# USB.net
KiCad netlist of a schematic drawn in Altium Designer
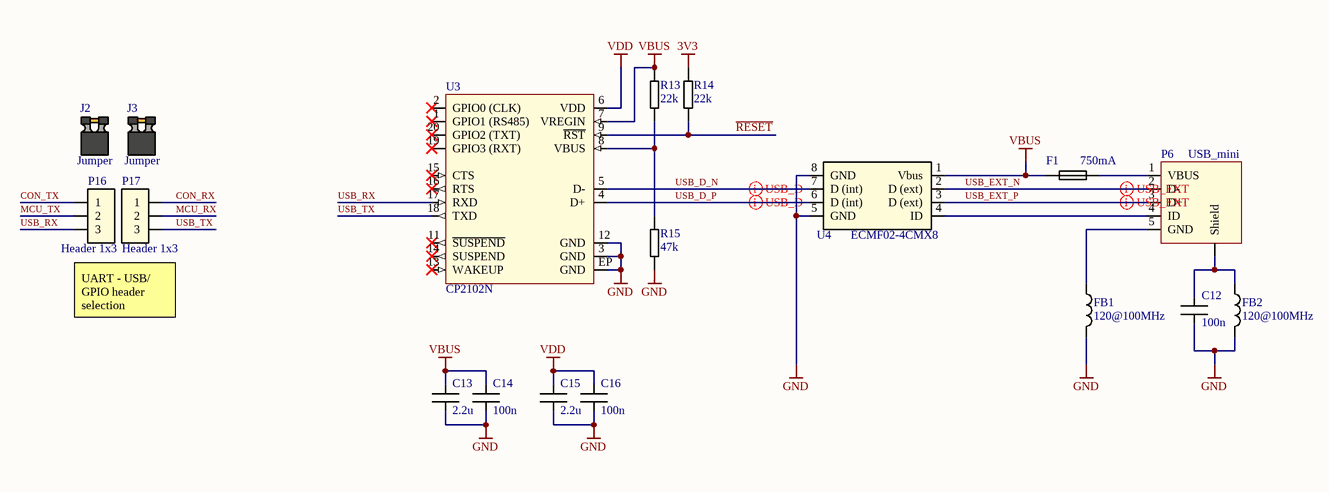
[diagram p0: USB.SchDoc]

(export (version "E")
  (design (tool "Eeschema 10.0.6"))
  (components
    (comp (ref "C12")
      (value "100n")
      (footprint "CAPC1005N")
      (description "0402 SMD Capacitor")
      (fields (field (name "TOLERANCE") "10%"))
      (libsource (lib "RLC") (part "Capacitor"))
    )
    (comp (ref "C13")
      (value "2.2u")
      (footprint "CAPC1005N")
      (description "0402 SMD Capacitor")
      (fields (field (name "TOLERANCE") "10%") (field (name "Comment") "Capacitor"))
      (libsource (lib "RLC") (part "Capacitor"))
    )
    (comp (ref "C14")
      (value "100n")
      (footprint "CAPC1005N")
      (description "0402 SMD Capacitor")
      (fields (field (name "TOLERANCE") "10%"))
      (libsource (lib "RLC") (part "Capacitor"))
    )
    (comp (ref "C15")
      (value "2.2u")
      (footprint "CAPC1005N")
      (description "0402 SMD Capacitor")
      (fields (field (name "TOLERANCE") "10%") (field (name "Comment") "Capacitor"))
      (libsource (lib "RLC") (part "Capacitor"))
    )
    (comp (ref "C16")
      (value "100n")
      (footprint "CAPC1005N")
      (description "0402 SMD Capacitor")
      (fields (field (name "TOLERANCE") "10%"))
      (libsource (lib "RLC") (part "Capacitor"))
    )
    (comp (ref "F1")
      (value "PTC Fuse")
      (footprint "RESC2012N")
      (description "PTC Fuse 750mA")
      (fields (field (name "STAND CURRENT") "750mA"))
      (libsource (lib "PTC_Fuse") (part "SD075-16"))
    )
    (comp (ref "FB1")
      (value "120@100MHz")
      (footprint "INDC1005N")
      (description "Ferrite Bead")
      (fields (field (name "TOLERANCE") "25%"))
      (libsource (lib "RLC") (part "Inductor"))
    )
    (comp (ref "FB2")
      (value "120@100MHz")
      (footprint "INDC1005N")
      (description "Ferrite Bead")
      (fields (field (name "TOLERANCE") "25%"))
      (libsource (lib "RLC") (part "Inductor"))
    )
    (comp (ref "J2")
      (value "Jumper")
      (footprint "JUMPER-B")
      (description "1x2, 2.54mm Black header jumper")
      (libsource (lib "Ninigi_Jumpers") (part "Header Jumper Black"))
    )
    (comp (ref "J3")
      (value "Jumper")
      (footprint "JUMPER-B")
      (description "1x2, 2.54mm Black header jumper")
      (libsource (lib "Ninigi_Jumpers") (part "Header Jumper Black"))
    )
    (comp (ref "P6")
      (value "USB_mini")
      (footprint "MUSB-B5-S-RA-TSMT-CS1")
      (description "Gniazdo; USB B mini; SMT; poziome; V: USB 2.0; złocony")
      (libsource (lib "Adam Tech Connectors") (part "MUSB-B5-S-RA-TSMT-CS1"))
    )
    (comp (ref "P16")
      (value "Header 1x3")
      (footprint "Header 1x3, Male, 2.54mm, Straight, THT")
      (description "Pin header, 1x3, 2.54mm")
      (libsource (lib "") (part "Header 1x3_1"))
    )
    (comp (ref "P17")
      (value "Header 1x3")
      (footprint "Header 1x3, Male, 2.54mm, Straight, THT")
      (description "Pin header, 1x3, 2.54mm")
      (libsource (lib "Header") (part "Header 1x3"))
    )
    (comp (ref "R13")
      (value "22k")
      (footprint "RESC1005N")
      (description "0402 Film SMD Resistor")
      (fields (field (name "TOLERANCE") "1%") (field (name "POWER") "0.1W"))
      (libsource (lib "RLC") (part "Resistor"))
    )
    (comp (ref "R14")
      (value "22k")
      (footprint "RESC1005N")
      (description "0402 Film SMD Resistor")
      (fields (field (name "TOLERANCE") "1%") (field (name "POWER") "0.1W"))
      (libsource (lib "RLC") (part "Resistor"))
    )
    (comp (ref "R15")
      (value "47k")
      (footprint "RESC1005N")
      (description "0402 Film SMD Resistor")
      (fields (field (name "TOLERANCE") "1%") (field (name "POWER") "0.1W"))
      (libsource (lib "RLC") (part "Resistor"))
    )
    (comp (ref "U3")
      (value "CP2102N")
      (footprint "QFN-20")
      (description "USB Interface IC USBXpress - USB to UART Bridge QFN20")
      (libsource (lib "SiliconLabs") (part "CP2102N"))
    )
    (comp (ref "U4")
      (value "ECMF02-4CMX8")
      (footprint "uQFN-8")
      (description "STMicroelectronics Common Mode Filter with ESD protection, USB compatible")
      (libsource (lib "STMicroelectronics_Protective") (part "ECMF02-4CMX8"))
    )
  )
  (nets
    (net (code "1") (name "/CON_RX") (class "Default")
      (node (ref "P17") (pin "1") (pinfunction "1_1") (pintype "passive"))
    )
    (net (code "2") (name "/CON_TX") (class "Default")
      (node (ref "P16") (pin "1") (pinfunction "1_1") (pintype "passive"))
    )
    (net (code "3") (name "/MCU_RX") (class "Default")
      (node (ref "P17") (pin "2") (pinfunction "2_2") (pintype "passive"))
    )
    (net (code "4") (name "/MCU_TX") (class "Default")
      (node (ref "P16") (pin "2") (pinfunction "2_2") (pintype "passive"))
    )
    (net (code "5") (name "/USB_D_N") (class "Default")
      (node (ref "U3") (pin "5") (pinfunction "D-_5") (pintype "bidirectional"))
      (node (ref "U4") (pin "7") (pinfunction "D_(int)_7") (pintype "passive"))
    )
    (net (code "6") (name "/USB_D_P") (class "Default")
      (node (ref "U3") (pin "4") (pinfunction "D+_4") (pintype "bidirectional"))
      (node (ref "U4") (pin "6") (pinfunction "D_(int)_6") (pintype "passive"))
    )
    (net (code "7") (name "/USB_EXT_N") (class "Default")
      (node (ref "P6") (pin "2") (pinfunction "D-_2") (pintype "bidirectional"))
      (node (ref "U4") (pin "2") (pinfunction "D_(ext)_2") (pintype "passive"))
    )
    (net (code "8") (name "/USB_EXT_P") (class "Default")
      (node (ref "P6") (pin "3") (pinfunction "D+_3") (pintype "bidirectional"))
      (node (ref "U4") (pin "3") (pinfunction "D_(ext)_3") (pintype "passive"))
    )
    (net (code "9") (name "/USB_RX") (class "Default")
      (node (ref "P16") (pin "3") (pinfunction "3_3") (pintype "passive"))
      (node (ref "U3") (pin "17") (pinfunction "RXD_17") (pintype "input"))
    )
    (net (code "10") (name "/USB_TX") (class "Default")
      (node (ref "P17") (pin "3") (pinfunction "3_3") (pintype "passive"))
      (node (ref "U3") (pin "18") (pinfunction "TXD_18") (pintype "output"))
    )
    (net (code "11") (name "/~{RESET}") (class "Default")
      (node (ref "R14") (pin "1") (pinfunction "1_1") (pintype "passive"))
      (node (ref "U3") (pin "9") (pinfunction "~{RST}_9") (pintype "input"))
    )
    (net (code "12") (name "3V3") (class "Default")
      (node (ref "R14") (pin "2") (pinfunction "2_2") (pintype "passive"))
    )
    (net (code "13") (name "GND") (class "Default")
      (node (ref "C12") (pin "1") (pinfunction "1_1") (pintype "passive"))
      (node (ref "C13") (pin "1") (pinfunction "1_1") (pintype "passive"))
      (node (ref "C14") (pin "1") (pinfunction "1_1") (pintype "passive"))
      (node (ref "C15") (pin "1") (pinfunction "1_1") (pintype "passive"))
      (node (ref "C16") (pin "1") (pinfunction "1_1") (pintype "passive"))
      (node (ref "FB1") (pin "2") (pinfunction "2_2") (pintype "passive"))
      (node (ref "FB2") (pin "2") (pinfunction "2_2") (pintype "passive"))
      (node (ref "R15") (pin "1") (pinfunction "1_1") (pintype "passive"))
      (node (ref "U3") (pin "12") (pinfunction "GND_12") (pintype "power_in"))
      (node (ref "U3") (pin "3") (pinfunction "GND_3") (pintype "power_in"))
      (node (ref "U3") (pin "EP") (pinfunction "GND_EP") (pintype "power_in"))
      (node (ref "U4") (pin "5") (pinfunction "GND_5") (pintype "passive"))
      (node (ref "U4") (pin "8") (pinfunction "GND_8") (pintype "passive"))
    )
    (net (code "14") (name "Net-(P6-GND)") (class "Default")
      (node (ref "FB1") (pin "1") (pinfunction "1_1") (pintype "passive"))
      (node (ref "P6") (pin "5") (pinfunction "GND_5") (pintype "power_in"))
    )
    (net (code "15") (name "Net-(P6-ID)") (class "Default")
      (node (ref "P6") (pin "4") (pinfunction "ID_4") (pintype "bidirectional"))
      (node (ref "U4") (pin "4") (pinfunction "ID_4") (pintype "passive"))
    )
    (net (code "16") (name "Net-(P6-Shield)") (class "Default")
      (node (ref "C12") (pin "2") (pinfunction "2_2") (pintype "passive"))
      (node (ref "FB2") (pin "1") (pinfunction "1_1") (pintype "passive"))
      (node (ref "P6") (pin "0") (pinfunction "Shield_0") (pintype "passive"))
    )
    (net (code "17") (name "Net-(P6-VBUS)") (class "Default")
      (node (ref "F1") (pin "2") (pinfunction "2_2") (pintype "passive"))
      (node (ref "P6") (pin "1") (pinfunction "VBUS_1") (pintype "power_in"))
    )
    (net (code "18") (name "Net-(U3-VBUS)") (class "Default")
      (node (ref "R13") (pin "1") (pinfunction "1_1") (pintype "passive"))
      (node (ref "R15") (pin "2") (pinfunction "2_2") (pintype "passive"))
      (node (ref "U3") (pin "8") (pinfunction "VBUS_8") (pintype "input"))
    )
    (net (code "19") (name "VBUS") (class "Default")
      (node (ref "C13") (pin "2") (pinfunction "2_2") (pintype "passive"))
      (node (ref "C14") (pin "2") (pinfunction "2_2") (pintype "passive"))
      (node (ref "F1") (pin "1") (pinfunction "1_1") (pintype "passive"))
      (node (ref "R13") (pin "2") (pinfunction "2_2") (pintype "passive"))
      (node (ref "U3") (pin "7") (pinfunction "VREGIN_7") (pintype "input"))
      (node (ref "U4") (pin "1") (pinfunction "Vbus_1") (pintype "passive"))
    )
    (net (code "20") (name "VDD") (class "Default")
      (node (ref "C15") (pin "2") (pinfunction "2_2") (pintype "passive"))
      (node (ref "C16") (pin "2") (pinfunction "2_2") (pintype "passive"))
      (node (ref "U3") (pin "6") (pinfunction "VDD_6") (pintype "power_in"))
    )
    (net (code "21") (name "unconnected-(U3-CTS-Pad15)") (class "Default")
      (node (ref "U3") (pin "15") (pinfunction "CTS_15") (pintype "input+no_connect"))
    )
    (net (code "22") (name "unconnected-(U3-GPIO0_(CLK)-Pad2)") (class "Default")
      (node (ref "U3") (pin "2") (pinfunction "GPIO0_(CLK)_2") (pintype "bidirectional+no_connect"))
    )
    (net (code "23") (name "unconnected-(U3-GPIO1_(RS485)-Pad1)") (class "Default")
      (node (ref "U3") (pin "1") (pinfunction "GPIO1_(RS485)_1") (pintype "bidirectional+no_connect"))
    )
    (net (code "24") (name "unconnected-(U3-GPIO2_(TXT)-Pad20)") (class "Default")
      (node (ref "U3") (pin "20") (pinfunction "GPIO2_(TXT)_20") (pintype "bidirectional+no_connect"))
    )
    (net (code "25") (name "unconnected-(U3-GPIO3_(RXT)-Pad19)") (class "Default")
      (node (ref "U3") (pin "19") (pinfunction "GPIO3_(RXT)_19") (pintype "bidirectional+no_connect"))
    )
    (net (code "26") (name "unconnected-(U3-RTS-Pad16)") (class "Default")
      (node (ref "U3") (pin "16") (pinfunction "RTS_16") (pintype "output+no_connect"))
    )
    (net (code "27") (name "unconnected-(U3-SUSPEND-Pad14)") (class "Default")
      (node (ref "U3") (pin "14") (pinfunction "SUSPEND_14") (pintype "output+no_connect"))
    )
    (net (code "28") (name "unconnected-(U3-WAKEUP-Pad13)") (class "Default")
      (node (ref "U3") (pin "13") (pinfunction "WAKEUP_13") (pintype "input+no_connect"))
    )
    (net (code "29") (name "unconnected-(U3-~{SUSPEND}-Pad11)") (class "Default")
      (node (ref "U3") (pin "11") (pinfunction "~{SUSPEND}_11") (pintype "output+no_connect"))
    )
  )
)
